# ETH10M100_MAGNET_RJ45.net
KiCad netlist of a schematic drawn in Altium Designer
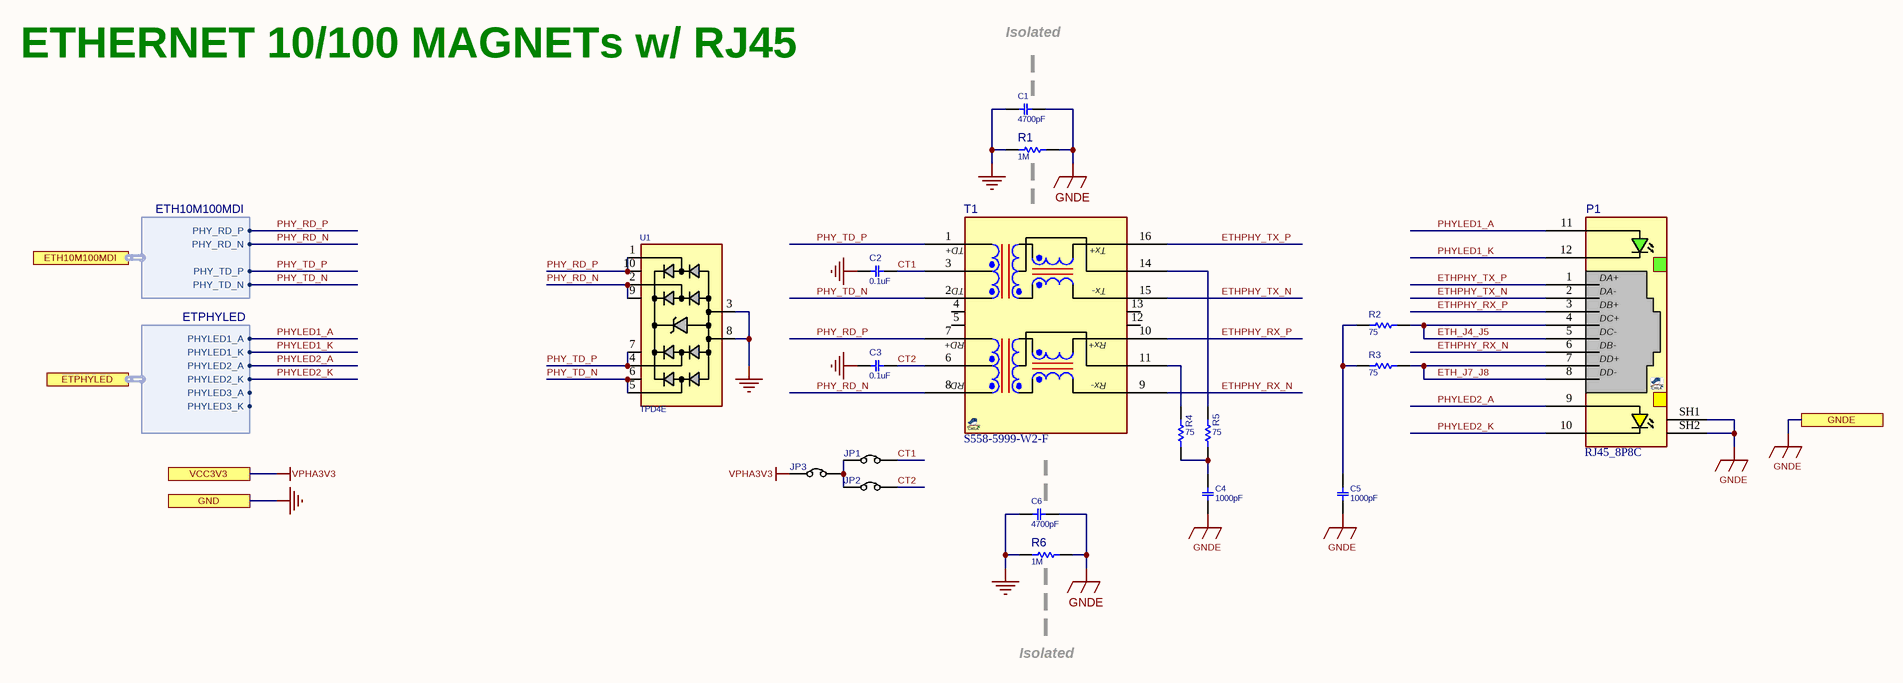
[diagram p0: ETH10M100_MAGNET_RJ45.SchDoc]

(export (version "E")
  (design (tool "Eeschema 10.0.6"))
  (components
    (comp (ref "C1")
      (value "4700pF")
      (footprint "C1206")
      (description "CAP, MLCC")
      (fields (field (name "MANF_P#") "NV1206B472K202CEGN") (field (name "MANF") "KEMET"))
      (libsource (lib "mlcc_smd_passive") (part "CAP_SMD_MLCC_68n1kv"))
    )
    (comp (ref "C2")
      (value "0.1uF")
      (footprint "C0402")
      (description "CAP, MLCC")
      (libsource (lib "mlcc_smd_passive") (part "CAP_SMD_MLCC_22n50V"))
    )
    (comp (ref "C3")
      (value "0.1uF")
      (footprint "C0402")
      (description "CAP, MLCC")
      (libsource (lib "mlcc_smd_passive") (part "CAP_SMD_MLCC_22n50V"))
    )
    (comp (ref "C4")
      (value "1000pF")
      (footprint "C1206")
      (description "CAP, MLCC")
      (fields (field (name "MANF_P#") "1206B102K202NT"))
      (libsource (lib "mlcc_smd_passive") (part "CAP_SMD_MLCC_22n50V"))
    )
    (comp (ref "C5")
      (value "1000pF")
      (footprint "C1206")
      (description "CAP, MLCC")
      (fields (field (name "MANF_P#") "1206B102K202NT"))
      (libsource (lib "mlcc_smd_passive") (part "CAP_SMD_MLCC_22n50V"))
    )
    (comp (ref "C6")
      (value "4700pF")
      (footprint "C1206")
      (description "CAP, MLCC")
      (fields (field (name "MANF_P#") "NV1206B472K202CEGN") (field (name "MANF") "KEMET"))
      (libsource (lib "mlcc_smd_passive") (part "CAP_SMD_MLCC_68n1kv"))
    )
    (comp (ref "JP1")
      (value "JMPSOLDER")
      (footprint "JP_30X50")
      (description "JUMPER, HEADER 2PIN")
      (fields (field (name "MANF") "MANF") (field (name "MANF_P#") "MANF_P#"))
      (libsource (lib "test-tp_jumper") (part "JUMPER_SOLDER"))
    )
    (comp (ref "JP2")
      (value "JMPSOLDER")
      (footprint "JP_30X50")
      (description "JUMPER, HEADER 2PIN")
      (fields (field (name "MANF") "MANF") (field (name "MANF_P#") "MANF_P#"))
      (libsource (lib "test-tp_jumper") (part "JUMPER_SOLDER"))
    )
    (comp (ref "JP3")
      (value "JMPSOLDER")
      (footprint "JP_30X50")
      (description "JUMPER, HEADER 2PIN")
      (fields (field (name "MANF") "MANF") (field (name "MANF_P#") "MANF_P#"))
      (libsource (lib "test-tp_jumper") (part "JUMPER_SOLDER"))
    )
    (comp (ref "P1")
      (value "RJ45_8P8C")
      (footprint "RJ45_8S_RA_TU_L")
      (description "RJ45, 8P+LED, SHIELDED, RightAngle, TabUP")
      (fields (field (name "MANF") "WURTH") (field (name "MANF_P#") "615008137421"))
      (libsource (lib "conn_rj_ModularJack") (part "RJ45_8S_RA_TU_L"))
    )
    (comp (ref "R1")
      (value "1M")
      (footprint "R2512")
      (description "RESISTOR, SMD")
      (fields (field (name "MANF_P#") "FRC2512J105 TS"))
      (libsource (lib "chila_passive") (part "RES_SMD"))
    )
    (comp (ref "R2")
      (value "75")
      (footprint "R0603O")
      (description "RESISTOR, SMD, THICK FILM, YAGEO")
      (fields (field (name "MANF_P#") "RC0402FR-071KL") (field (name "MANF") "Yageo"))
      (libsource (lib "res_smd_Yageo0402_thickfilm") (part "RES_SMD_1K_0402YK"))
    )
    (comp (ref "R3")
      (value "75")
      (footprint "R0603O")
      (description "RESISTOR, SMD, THICK FILM, YAGEO")
      (fields (field (name "MANF_P#") "RC0402FR-071KL") (field (name "MANF") "Yageo"))
      (libsource (lib "res_smd_Yageo0402_thickfilm") (part "RES_SMD_1K_0402YK"))
    )
    (comp (ref "R4")
      (value "75")
      (footprint "R0603O")
      (description "RESISTOR, SMD, THICK FILM, YAGEO")
      (fields (field (name "MANF_P#") "RC0402FR-071KL") (field (name "MANF") "Yageo"))
      (libsource (lib "res_smd_Yageo0402_thickfilm") (part "RES_SMD_1K_0402YK"))
    )
    (comp (ref "R5")
      (value "75")
      (footprint "R0603O")
      (description "RESISTOR, SMD, THICK FILM, YAGEO")
      (fields (field (name "MANF_P#") "RC0402FR-071KL") (field (name "MANF") "Yageo"))
      (libsource (lib "res_smd_Yageo0402_thickfilm") (part "RES_SMD_1K_0402YK"))
    )
    (comp (ref "R6")
      (value "1M")
      (footprint "R2512")
      (description "RESISTOR, SMD")
      (fields (field (name "MANF_P#") "FRC2512J105 TS"))
      (libsource (lib "chila_passive") (part "RES_SMD"))
    )
    (comp (ref "T1")
      (value "S558-5999-W2-F")
      (footprint "SO_16_7W6H")
      (description "Transformer, LAN, 10/100 Base-T, 1CT:1CT, 350uH")
      (fields (field (name "MANF") "Bel"))
      (libsource (lib "transformer_ethernet") (part "S558-5999-W2-F_SO16"))
    )
    (comp (ref "U1")
      (value "TPD4E")
      (footprint "SON50_10_2510")
      (description "TVS, ESD PROTECT, 4CH,")
      (fields (field (name "MANF_P#") "TPD4E05U06DQA") (field (name "MANF") "Texas Instruments"))
      (libsource (lib "protect_tvs_esd_fuse") (part "TVS_X4_TPD4E05U06"))
    )
  )
  (nets
    (net (code "3") (name "/CT1") (class "Default")
      (node (ref "C2") (pin "2") (pinfunction "2_2") (pintype "passive"))
      (node (ref "JP1") (pin "2") (pinfunction "2_2") (pintype "passive"))
      (node (ref "T1") (pin "3") (pinfunction "TDCT_3") (pintype "passive"))
    )
    (net (code "4") (name "/CT2") (class "Default")
      (node (ref "C3") (pin "2") (pinfunction "2_2") (pintype "passive"))
      (node (ref "JP2") (pin "2") (pinfunction "2_2") (pintype "passive"))
      (node (ref "T1") (pin "6") (pinfunction "RDCT_6") (pintype "passive"))
    )
    (net (code "5") (name "/ETHPHY_RX_N") (class "Default")
      (node (ref "P1") (pin "6") (pinfunction "DB-_6") (pintype "passive"))
      (node (ref "T1") (pin "9") (pinfunction "RX-_9") (pintype "passive"))
    )
    (net (code "6") (name "/ETHPHY_RX_P") (class "Default")
      (node (ref "P1") (pin "3") (pinfunction "DB+_3") (pintype "passive"))
      (node (ref "T1") (pin "10") (pinfunction "RX+_10") (pintype "passive"))
    )
    (net (code "7") (name "/ETHPHY_TX_N") (class "Default")
      (node (ref "P1") (pin "2") (pinfunction "DA-_2") (pintype "passive"))
      (node (ref "T1") (pin "15") (pinfunction "TX-_15") (pintype "passive"))
    )
    (net (code "8") (name "/ETHPHY_TX_P") (class "Default")
      (node (ref "P1") (pin "1") (pinfunction "DA+_1") (pintype "passive"))
      (node (ref "T1") (pin "16") (pinfunction "TX+_16") (pintype "passive"))
    )
    (net (code "9") (name "/ETH_J4_J5") (class "Default")
      (node (ref "P1") (pin "4") (pinfunction "DC+_4") (pintype "passive"))
      (node (ref "P1") (pin "5") (pinfunction "DC-_5") (pintype "passive"))
      (node (ref "R2") (pin "2") (pinfunction "2_2") (pintype "passive"))
    )
    (net (code "10") (name "/ETH_J7_J8") (class "Default")
      (node (ref "P1") (pin "7") (pinfunction "DD+_7") (pintype "passive"))
      (node (ref "P1") (pin "8") (pinfunction "DD-_8") (pintype "passive"))
      (node (ref "R3") (pin "2") (pinfunction "2_2") (pintype "passive"))
    )
    (net (code "11") (name "/PHYLED1_A") (class "Default")
      (node (ref "P1") (pin "11") (pinfunction "GLED+_11") (pintype "passive"))
    )
    (net (code "12") (name "/PHYLED1_K") (class "Default")
      (node (ref "P1") (pin "12") (pinfunction "GLED-_12") (pintype "passive"))
    )
    (net (code "13") (name "/PHYLED2_A") (class "Default")
      (node (ref "P1") (pin "9") (pinfunction "YLED+_9") (pintype "passive"))
    )
    (net (code "14") (name "/PHYLED2_K") (class "Default")
      (node (ref "P1") (pin "10") (pinfunction "YLED-_10") (pintype "passive"))
    )
    (net (code "15") (name "/PHY_RD_N") (class "Default")
      (node (ref "T1") (pin "8") (pinfunction "RD-_8") (pintype "passive"))
      (node (ref "U1") (pin "2") (pinfunction "2_2") (pintype "passive"))
      (node (ref "U1") (pin "9") (pinfunction "9_9") (pintype "passive"))
    )
    (net (code "16") (name "/PHY_RD_P") (class "Default")
      (node (ref "T1") (pin "7") (pinfunction "RD+_7") (pintype "passive"))
      (node (ref "U1") (pin "1") (pinfunction "1_1") (pintype "passive"))
      (node (ref "U1") (pin "10") (pinfunction "10_10") (pintype "passive"))
    )
    (net (code "17") (name "/PHY_TD_N") (class "Default")
      (node (ref "T1") (pin "2") (pinfunction "TD-_2") (pintype "passive"))
      (node (ref "U1") (pin "5") (pinfunction "5_5") (pintype "passive"))
      (node (ref "U1") (pin "6") (pinfunction "6_6") (pintype "passive"))
    )
    (net (code "18") (name "/PHY_TD_P") (class "Default")
      (node (ref "T1") (pin "1") (pinfunction "TD+_1") (pintype "passive"))
      (node (ref "U1") (pin "4") (pinfunction "4_4") (pintype "passive"))
      (node (ref "U1") (pin "7") (pinfunction "7_7") (pintype "passive"))
    )
    (net (code "21") (name "GND") (class "Default")
      (node (ref "C1") (pin "1") (pinfunction "1_1") (pintype "passive"))
      (node (ref "C2") (pin "1") (pinfunction "1_1") (pintype "passive"))
      (node (ref "C3") (pin "1") (pinfunction "1_1") (pintype "passive"))
      (node (ref "C6") (pin "1") (pinfunction "1_1") (pintype "passive"))
      (node (ref "R1") (pin "2") (pinfunction "2_2") (pintype "passive"))
      (node (ref "R6") (pin "2") (pinfunction "2_2") (pintype "passive"))
      (node (ref "U1") (pin "3") (pinfunction "3_3") (pintype "passive"))
      (node (ref "U1") (pin "8") (pinfunction "8_8") (pintype "passive"))
    )
    (net (code "22") (name "GNDE") (class "Default")
      (node (ref "C1") (pin "2") (pinfunction "2_2") (pintype "passive"))
      (node (ref "C4") (pin "2") (pinfunction "2_2") (pintype "passive"))
      (node (ref "C5") (pin "2") (pinfunction "2_2") (pintype "passive"))
      (node (ref "C6") (pin "2") (pinfunction "2_2") (pintype "passive"))
      (node (ref "P1") (pin "SH1") (pinfunction "SH1_SH1") (pintype "passive"))
      (node (ref "P1") (pin "SH2") (pinfunction "SH2_SH2") (pintype "passive"))
      (node (ref "R1") (pin "1") (pinfunction "1_1") (pintype "passive"))
      (node (ref "R6") (pin "1") (pinfunction "1_1") (pintype "passive"))
    )
    (net (code "23") (name "Net-(C4-Pad1)") (class "Default")
      (node (ref "C4") (pin "1") (pinfunction "1_1") (pintype "passive"))
      (node (ref "R4") (pin "2") (pinfunction "2_2") (pintype "passive"))
      (node (ref "R5") (pin "2") (pinfunction "2_2") (pintype "passive"))
    )
    (net (code "24") (name "Net-(C5-Pad1)") (class "Default")
      (node (ref "C5") (pin "1") (pinfunction "1_1") (pintype "passive"))
      (node (ref "R2") (pin "1") (pinfunction "1_1") (pintype "passive"))
      (node (ref "R3") (pin "1") (pinfunction "1_1") (pintype "passive"))
    )
    (net (code "25") (name "Net-(JP1-Pad1)") (class "Default")
      (node (ref "JP1") (pin "1") (pinfunction "1_1") (pintype "passive"))
      (node (ref "JP2") (pin "1") (pinfunction "1_1") (pintype "passive"))
      (node (ref "JP3") (pin "2") (pinfunction "2_2") (pintype "passive"))
    )
    (net (code "26") (name "Net-(T1-RXCT)") (class "Default")
      (node (ref "R4") (pin "1") (pinfunction "1_1") (pintype "passive"))
      (node (ref "T1") (pin "11") (pinfunction "RXCT_11") (pintype "passive"))
    )
    (net (code "27") (name "Net-(T1-TXCT)") (class "Default")
      (node (ref "R5") (pin "1") (pinfunction "1_1") (pintype "passive"))
      (node (ref "T1") (pin "14") (pinfunction "TXCT_14") (pintype "passive"))
    )
    (net (code "28") (name "VPHA3V3") (class "Default")
      (node (ref "JP3") (pin "1") (pinfunction "1_1") (pintype "passive"))
    )
    (net (code "29") (name "unconnected-(T1-NC_1-Pad4)") (class "Default")
      (node (ref "T1") (pin "4") (pinfunction "NC_1_4") (pintype "passive"))
    )
    (net (code "30") (name "unconnected-(T1-NC_2-Pad5)") (class "Default")
      (node (ref "T1") (pin "5") (pinfunction "NC_2_5") (pintype "passive"))
    )
    (net (code "31") (name "unconnected-(T1-NC_3-Pad12)") (class "Default")
      (node (ref "T1") (pin "12") (pinfunction "NC_3_12") (pintype "passive"))
    )
    (net (code "32") (name "unconnected-(T1-NC_4-Pad13)") (class "Default")
      (node (ref "T1") (pin "13") (pinfunction "NC_4_13") (pintype "passive"))
    )
  )
)
